# obc_flash.net
KiCad netlist of a schematic drawn in Altium Designer
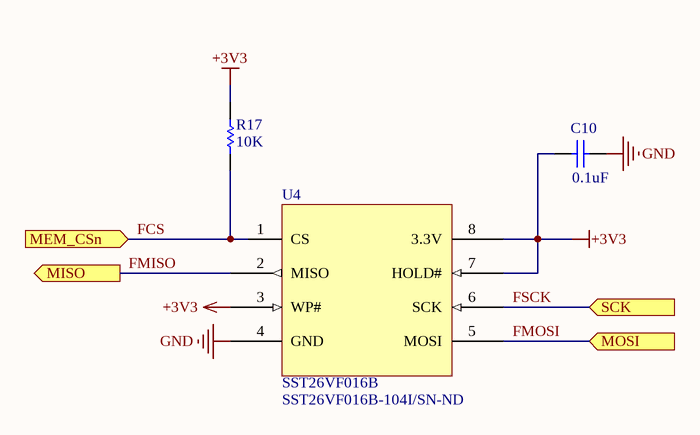
[diagram p0: obc_flash.SchDoc]

(export (version "E")
  (design (tool "Eeschema 10.0.6"))
  (components
    (comp (ref "C10")
      (value "0.1uF")
      (footprint "CAP0603R")
      (description "0603 capacitor")
      (fields (field (name "Comment") "0603"))
      (libsource (lib "heron-general") (part "CAP0603"))
    )
    (comp (ref "R17")
      (value "10K")
      (footprint "RES0603R")
      (description "0603 resistor")
      (fields (field (name "Comment") "0603"))
      (libsource (lib "heron-general") (part "RES0603"))
    )
    (comp (ref "U4")
      (value "SST26VF016B")
      (footprint "SOIC127P500X600-8N")
      (description "2.5V/3.0V 16 Mbit Serial Quad I/O (SQI) Flash Memory")
      (fields (field (name "SUPPLIER PART NUMBER 1") "SST26VF016B-104I/SN-ND"))
      (libsource (lib "heron-general") (part "SST26VF016B"))
    )
  )
  (nets
    (net (code "1") (name "+3V3") (class "Default")
      (node (ref "C10") (pin "1") (pinfunction "1_1") (pintype "passive"))
      (node (ref "R17") (pin "2") (pinfunction "2_2") (pintype "passive"))
      (node (ref "U4") (pin "3") (pinfunction "WP#_3") (pintype "input"))
      (node (ref "U4") (pin "7") (pinfunction "HOLD#_7") (pintype "input"))
      (node (ref "U4") (pin "8") (pinfunction "3.3V_8") (pintype "power_in"))
    )
    (net (code "2") (name "/FCS") (class "Default")
      (node (ref "R17") (pin "1") (pinfunction "1_1") (pintype "passive"))
      (node (ref "U4") (pin "1") (pinfunction "CS_1") (pintype "passive"))
    )
    (net (code "3") (name "/FMISO") (class "Default")
      (node (ref "U4") (pin "2") (pinfunction "MISO_2") (pintype "output"))
    )
    (net (code "4") (name "/FMOSI") (class "Default")
      (node (ref "U4") (pin "5") (pinfunction "MOSI_5") (pintype "passive"))
    )
    (net (code "5") (name "/FSCK") (class "Default")
      (node (ref "U4") (pin "6") (pinfunction "SCK_6") (pintype "input"))
    )
    (net (code "6") (name "GND") (class "Default")
      (node (ref "C10") (pin "2") (pinfunction "2_2") (pintype "passive"))
      (node (ref "U4") (pin "4") (pinfunction "GND_4") (pintype "power_in"))
    )
  )
)
